# hvreg_spellman_2PS.net
KiCad netlist of a schematic drawn in EAGLE
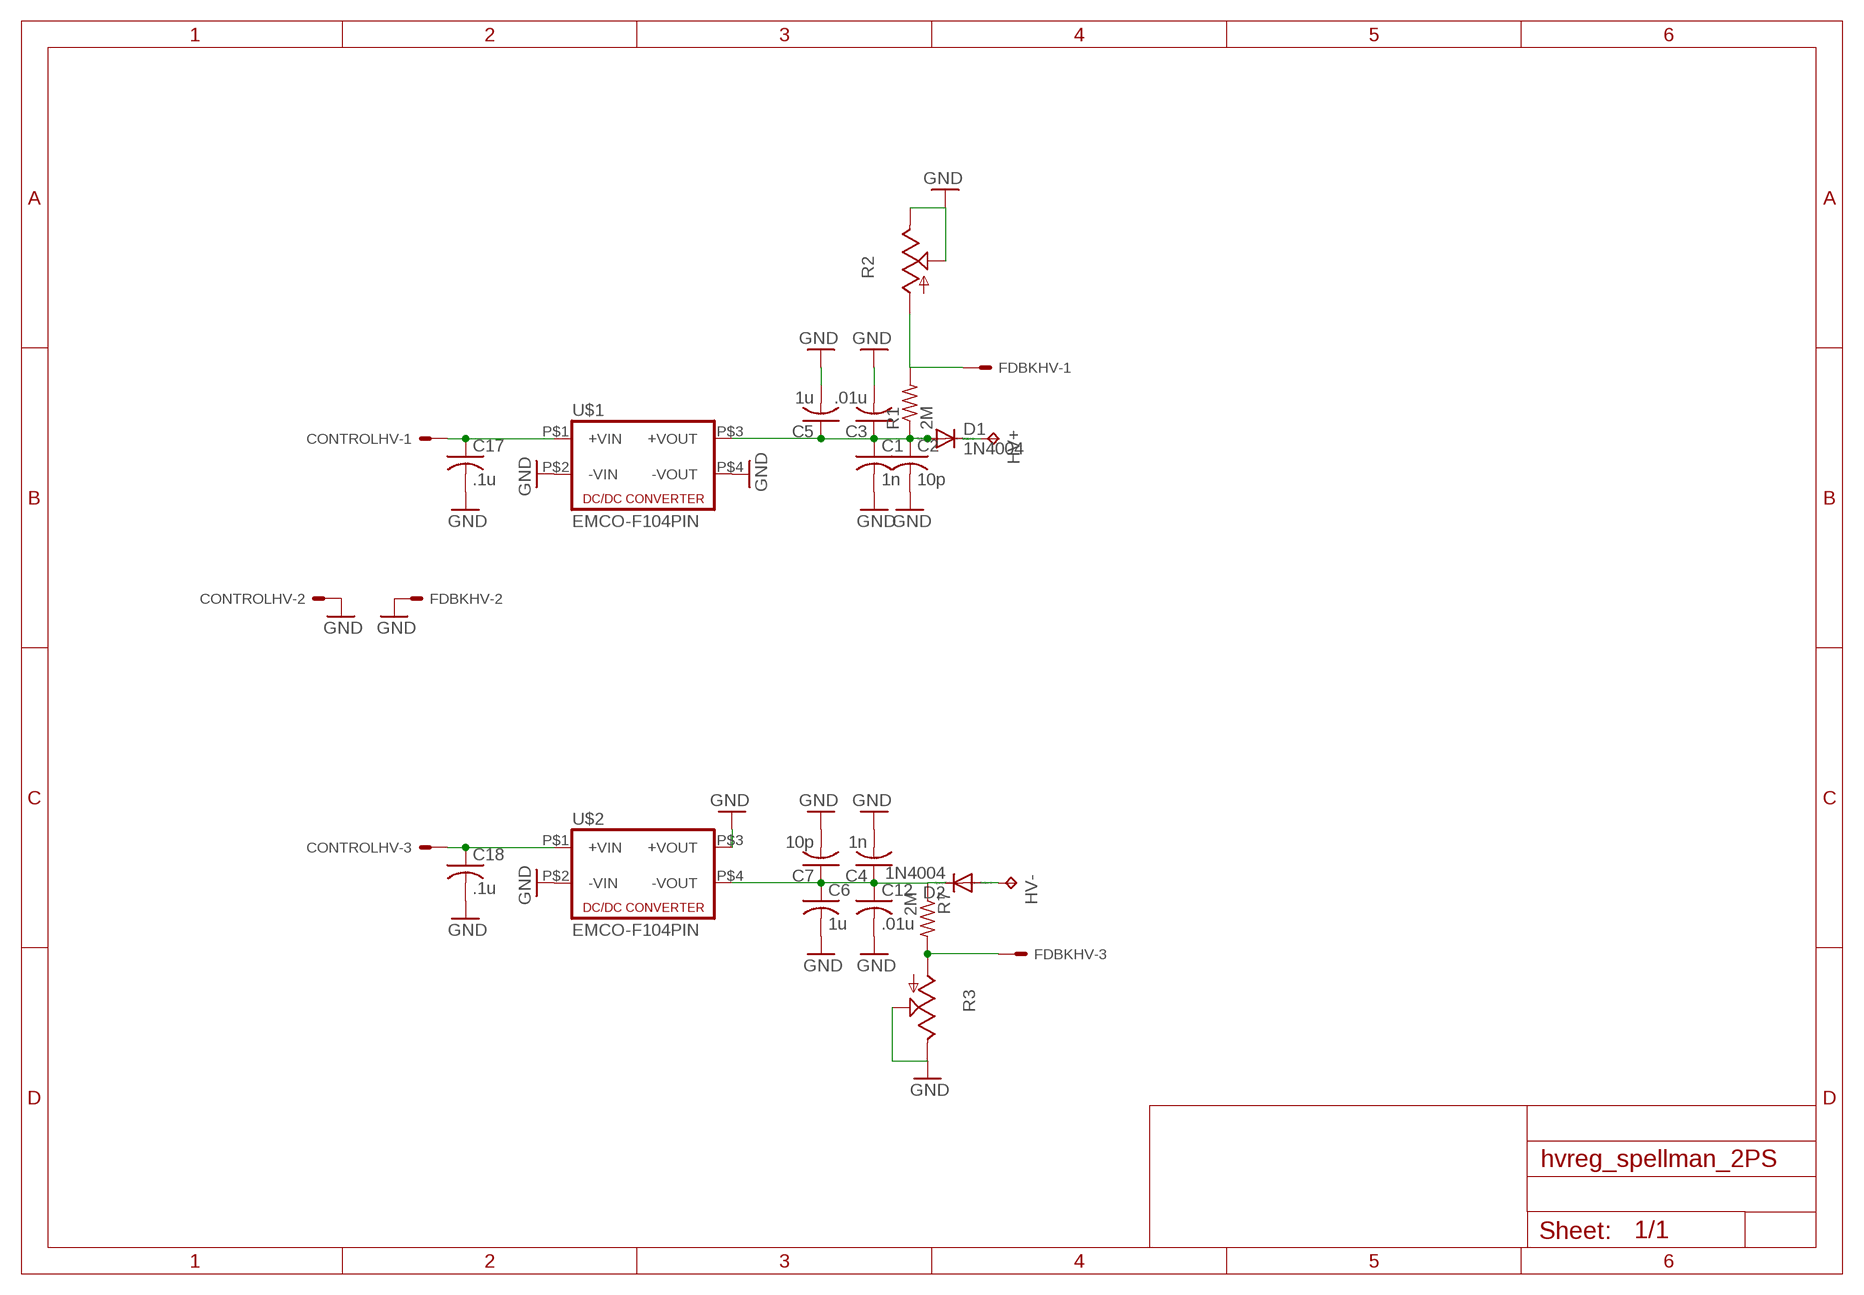
[diagram p0: schematic, sheet 1]

(export (version "E")
  (design (tool "Eeschema 10.0.6"))
  (components
    (comp (ref "C1")
      (value "1n")
      (footprint "eagle-import:C102-043X133")
      (libsource (lib "eagle-import") (part "C-US102-043X133"))
    )
    (comp (ref "C2")
      (value "10p")
      (footprint "eagle-import:C102-043X133")
      (libsource (lib "eagle-import") (part "C-US102-043X133"))
    )
    (comp (ref "C3")
      (value ".01u")
      (footprint "eagle-import:C102-043X133")
      (libsource (lib "eagle-import") (part "C-US102-043X133"))
    )
    (comp (ref "C4")
      (value "1n")
      (footprint "eagle-import:C102-043X133")
      (libsource (lib "eagle-import") (part "C-US102-043X133"))
    )
    (comp (ref "C5")
      (value "1u")
      (footprint "eagle-import:C275-205X316")
      (libsource (lib "eagle-import") (part "C-US275-205X316"))
    )
    (comp (ref "C6")
      (value "1u")
      (footprint "eagle-import:C275-205X316")
      (libsource (lib "eagle-import") (part "C-US275-205X316"))
    )
    (comp (ref "C7")
      (value "10p")
      (footprint "eagle-import:C102-043X133")
      (libsource (lib "eagle-import") (part "C-US102-043X133"))
    )
    (comp (ref "C12")
      (value ".01u")
      (footprint "eagle-import:C102-043X133")
      (libsource (lib "eagle-import") (part "C-US102-043X133"))
    )
    (comp (ref "C17")
      (value ".1u")
      (footprint "eagle-import:C225-113X268")
      (libsource (lib "eagle-import") (part "C-US225-113X268"))
    )
    (comp (ref "C18")
      (value ".1u")
      (footprint "eagle-import:C225-113X268")
      (libsource (lib "eagle-import") (part "C-US225-113X268"))
    )
    (comp (ref "CONTROLHV")
      (value "KK-156-3")
      (footprint "eagle-import:KK-156-3")
      (libsource (lib "eagle-import") (part "KK-156-3"))
    )
    (comp (ref "D1")
      (value "1N4004")
      (footprint "eagle-import:DO41-10")
      (libsource (lib "eagle-import") (part "1N4004"))
    )
    (comp (ref "D2")
      (value "1N4004")
      (footprint "eagle-import:DO41-10")
      (libsource (lib "eagle-import") (part "1N4004"))
    )
    (comp (ref "FDBKHV")
      (value "KK-156-3")
      (footprint "eagle-import:KK-156-3")
      (libsource (lib "eagle-import") (part "KK-156-3"))
    )
    (comp (ref "HV+")
      (value "TPPAD1-20Y")
      (footprint "eagle-import:P1-20Y")
      (libsource (lib "eagle-import") (part "TPPAD1-20Y"))
    )
    (comp (ref "HV-")
      (value "TPPAD1-20Y")
      (footprint "eagle-import:P1-20Y")
      (libsource (lib "eagle-import") (part "TPPAD1-20Y"))
    )
    (comp (ref "R1")
      (value "2M")
      (footprint "eagle-import:P0613_15")
      (libsource (lib "eagle-import") (part "R-US_0613/15"))
    )
    (comp (ref "R2")
      (value "TRIM_US-B90P")
      (footprint "eagle-import:SP19L")
      (libsource (lib "eagle-import") (part "TRIM_US-B90P"))
    )
    (comp (ref "R3")
      (value "TRIM_US-B90P")
      (footprint "eagle-import:SP19L")
      (libsource (lib "eagle-import") (part "TRIM_US-B90P"))
    )
    (comp (ref "R7")
      (value "2M")
      (footprint "eagle-import:P0613_15")
      (libsource (lib "eagle-import") (part "R-US_0613/15"))
    )
    (comp (ref "U$1")
      (value "EMCO-F104PIN")
      (footprint "eagle-import:EMCO-F")
      (libsource (lib "eagle-import") (part "EMCO-F104PIN"))
    )
    (comp (ref "U$2")
      (value "EMCO-F104PIN")
      (footprint "eagle-import:EMCO-F")
      (libsource (lib "eagle-import") (part "EMCO-F104PIN"))
    )
  )
  (nets
    (net (code "1") (name "GND") (class "Default")
      (node (ref "C1") (pin "2") (pinfunction "2_2") (pintype "passive"))
      (node (ref "C12") (pin "2") (pinfunction "2_2") (pintype "passive"))
      (node (ref "C17") (pin "2") (pinfunction "2_2") (pintype "passive"))
      (node (ref "C18") (pin "2") (pinfunction "2_2") (pintype "passive"))
      (node (ref "C2") (pin "2") (pinfunction "2_2") (pintype "passive"))
      (node (ref "C3") (pin "2") (pinfunction "2_2") (pintype "passive"))
      (node (ref "C4") (pin "2") (pinfunction "2_2") (pintype "passive"))
      (node (ref "C5") (pin "2") (pinfunction "2_2") (pintype "passive"))
      (node (ref "C6") (pin "2") (pinfunction "2_2") (pintype "passive"))
      (node (ref "C7") (pin "2") (pinfunction "2_2") (pintype "passive"))
      (node (ref "CONTROLHV") (pin "2") (pinfunction "S_2") (pintype "passive"))
      (node (ref "FDBKHV") (pin "2") (pinfunction "S_2") (pintype "passive"))
      (node (ref "R2") (pin "E") (pinfunction "E_E") (pintype "passive"))
      (node (ref "R2") (pin "S") (pinfunction "S_S") (pintype "passive"))
      (node (ref "R3") (pin "E") (pinfunction "E_E") (pintype "passive"))
      (node (ref "R3") (pin "S") (pinfunction "S_S") (pintype "passive"))
      (node (ref "U$1") (pin "P$2") (pinfunction "-VIN_P$2") (pintype "passive"))
      (node (ref "U$1") (pin "P$4") (pinfunction "-VOUT_P$4") (pintype "passive"))
      (node (ref "U$2") (pin "P$2") (pinfunction "-VIN_P$2") (pintype "passive"))
      (node (ref "U$2") (pin "P$3") (pinfunction "+VOUT_P$3") (pintype "passive"))
    )
    (net (code "2") (name "Net-(CONTROLHVA-S)") (class "Default")
      (node (ref "C17") (pin "1") (pinfunction "1_1") (pintype "passive"))
      (node (ref "CONTROLHV") (pin "1") (pinfunction "S_1") (pintype "passive"))
      (node (ref "U$1") (pin "P$1") (pinfunction "+VIN_P$1") (pintype "passive"))
    )
    (net (code "3") (name "Net-(CONTROLHVC-S)") (class "Default")
      (node (ref "C18") (pin "1") (pinfunction "1_1") (pintype "passive"))
      (node (ref "CONTROLHV") (pin "3") (pinfunction "S_3") (pintype "passive"))
      (node (ref "U$2") (pin "P$1") (pinfunction "+VIN_P$1") (pintype "passive"))
    )
    (net (code "4") (name "Net-(D1-PadC)") (class "Default")
      (node (ref "D1") (pin "C") (pinfunction "C_C") (pintype "passive"))
      (node (ref "HV+") (pin "TP") (pinfunction "TP_TP") (pintype "input"))
    )
    (net (code "5") (name "Net-(D2-PadA)") (class "Default")
      (node (ref "D2") (pin "A") (pinfunction "A_A") (pintype "passive"))
      (node (ref "HV-") (pin "TP") (pinfunction "TP_TP") (pintype "input"))
    )
    (net (code "6") (name "Net-(FDBKHVA-S)") (class "Default")
      (node (ref "FDBKHV") (pin "1") (pinfunction "S_1") (pintype "passive"))
      (node (ref "R1") (pin "2") (pinfunction "2_2") (pintype "passive"))
      (node (ref "R2") (pin "A") (pinfunction "A_A") (pintype "passive"))
    )
    (net (code "7") (name "Net-(FDBKHVC-S)") (class "Default")
      (node (ref "FDBKHV") (pin "3") (pinfunction "S_3") (pintype "passive"))
      (node (ref "R3") (pin "A") (pinfunction "A_A") (pintype "passive"))
      (node (ref "R7") (pin "2") (pinfunction "2_2") (pintype "passive"))
    )
    (net (code "8") (name "Net-(U$1-+VOUT)") (class "Default")
      (node (ref "C1") (pin "1") (pinfunction "1_1") (pintype "passive"))
      (node (ref "C2") (pin "1") (pinfunction "1_1") (pintype "passive"))
      (node (ref "C3") (pin "1") (pinfunction "1_1") (pintype "passive"))
      (node (ref "C5") (pin "1") (pinfunction "1_1") (pintype "passive"))
      (node (ref "D1") (pin "A") (pinfunction "A_A") (pintype "passive"))
      (node (ref "R1") (pin "1") (pinfunction "1_1") (pintype "passive"))
      (node (ref "U$1") (pin "P$3") (pinfunction "+VOUT_P$3") (pintype "passive"))
    )
    (net (code "9") (name "Net-(U$2--VOUT)") (class "Default")
      (node (ref "C12") (pin "1") (pinfunction "1_1") (pintype "passive"))
      (node (ref "C4") (pin "1") (pinfunction "1_1") (pintype "passive"))
      (node (ref "C6") (pin "1") (pinfunction "1_1") (pintype "passive"))
      (node (ref "C7") (pin "1") (pinfunction "1_1") (pintype "passive"))
      (node (ref "D2") (pin "C") (pinfunction "C_C") (pintype "passive"))
      (node (ref "R7") (pin "1") (pinfunction "1_1") (pintype "passive"))
      (node (ref "U$2") (pin "P$4") (pinfunction "-VOUT_P$4") (pintype "passive"))
    )
  )
)
